# CATS-FAT-Baro.net
KiCad netlist of a schematic drawn in Altium Designer
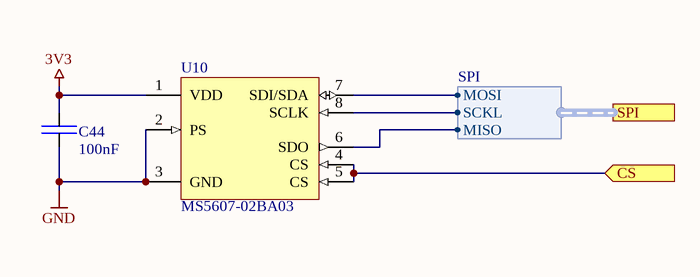
[diagram p0: CATS-FAT-Baro.SchDoc]

(export (version "E")
  (design (tool "Eeschema 10.0.6"))
  (components
    (comp (ref "C44")
      (value "100nF")
      (footprint "SMD Keramikkondensator 0603")
      (description "SMD Ceramic Capacitor E6")
      (libsource (lib "Ceramic Capacitors-E6") (part "E6 - 100nF"))
    )
    (comp (ref "U10")
      (value "MS5607-02BA03")
      (footprint "SMD IC BARO MS5607")
      (description "Barometric Pressure Sensor, with stainless\r\nsteel cap")
      (libsource (lib "Sensors") (part "MS5607-02BA03"))
    )
  )
  (nets
    (net (code "2") (name "/CS") (class "Default")
      (node (ref "U10") (pin "4") (pinfunction "CS_4") (pintype "input"))
      (node (ref "U10") (pin "5") (pinfunction "CS_5") (pintype "input"))
    )
    (net (code "3") (name "/MISO") (class "Default")
      (node (ref "U10") (pin "6") (pinfunction "SDO_6") (pintype "output"))
    )
    (net (code "4") (name "/MOSI") (class "Default")
      (node (ref "U10") (pin "7") (pinfunction "SDI/SDA_7") (pintype "bidirectional"))
    )
    (net (code "5") (name "/SCKL") (class "Default")
      (node (ref "U10") (pin "8") (pinfunction "SCLK_8") (pintype "input"))
    )
    (net (code "7") (name "3V3") (class "Default")
      (node (ref "C44") (pin "2") (pinfunction "2_2") (pintype "passive"))
      (node (ref "U10") (pin "1") (pinfunction "VDD_1") (pintype "passive"))
    )
    (net (code "8") (name "GND") (class "Default")
      (node (ref "C44") (pin "1") (pinfunction "1_1") (pintype "passive"))
      (node (ref "U10") (pin "2") (pinfunction "PS_2") (pintype "input"))
      (node (ref "U10") (pin "3") (pinfunction "GND_3") (pintype "passive"))
    )
  )
)
